# caphumidsens_rev4.net
KiCad netlist of a schematic drawn in EAGLE
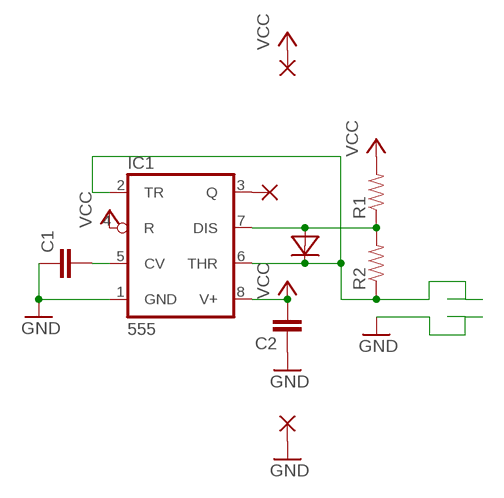
[diagram p0: schematic, sheet 1]

(export (version "E")
  (design (tool "Eeschema 10.0.6"))
  (components
    (comp (ref "C1")
      (value "CAP0805")
      (footprint "eagle-import:0805")
      (libsource (lib "eagle-import") (part "CAP0805"))
    )
    (comp (ref "C2")
      (value "CAP0805")
      (footprint "eagle-import:0805")
      (libsource (lib "eagle-import") (part "CAP0805"))
    )
    (comp (ref "D1")
      (value "DIODE_0805")
      (footprint "eagle-import:DIODE_0805")
      (libsource (lib "eagle-import") (part "DIODE_0805"))
    )
    (comp (ref "GND")
      (value "WIREPADSMD2,54-5,08")
      (footprint "eagle-import:SMD1,27-2,54")
      (libsource (lib "eagle-import") (part "SMD2"))
    )
    (comp (ref "IC1")
      (value "555")
      (footprint "eagle-import:SO08")
      (libsource (lib "eagle-import") (part "555DNE"))
    )
    (comp (ref "OUT")
      (value "WIREPADSMD2,54-5,08")
      (footprint "eagle-import:SMD1,27-2,54")
      (libsource (lib "eagle-import") (part "SMD2"))
    )
    (comp (ref "R1")
      (value "RESISTOR0805-RES")
      (footprint "eagle-import:0805")
      (libsource (lib "eagle-import") (part "RESISTOR0805-RES"))
    )
    (comp (ref "R2")
      (value "RESISTOR0805-RES")
      (footprint "eagle-import:0805")
      (libsource (lib "eagle-import") (part "RESISTOR0805-RES"))
    )
    (comp (ref "VCC")
      (value "WIREPADSMD2,54-5,08")
      (footprint "eagle-import:SMD1,27-2,54")
      (libsource (lib "eagle-import") (part "SMD2"))
    )
  )
  (nets
    (net (code "1") (name "GND") (class "Default")
      (node (ref "C1") (pin "1") (pinfunction "1_1") (pintype "passive"))
      (node (ref "C2") (pin "1") (pinfunction "1_1") (pintype "passive"))
      (node (ref "GND") (pin "1") (pinfunction "P_1") (pintype "passive"))
      (node (ref "IC1") (pin "1") (pinfunction "GND_1") (pintype "power_in"))
    )
    (net (code "2") (name "Net-(D1-A)") (class "Default")
      (node (ref "D1") (pin "2") (pinfunction "A_2") (pintype "passive"))
      (node (ref "IC1") (pin "7") (pinfunction "DIS_7") (pintype "input"))
      (node (ref "R1") (pin "1") (pinfunction "1_1") (pintype "passive"))
      (node (ref "R2") (pin "2") (pinfunction "2_2") (pintype "passive"))
    )
    (net (code "3") (name "Net-(D1-C)") (class "Default")
      (node (ref "D1") (pin "1") (pinfunction "C_1") (pintype "passive"))
      (node (ref "IC1") (pin "2") (pinfunction "TR_2") (pintype "input"))
      (node (ref "IC1") (pin "6") (pinfunction "THR_6") (pintype "input"))
      (node (ref "R2") (pin "1") (pinfunction "1_1") (pintype "passive"))
    )
    (net (code "4") (name "Net-(IC1-CV)") (class "Default")
      (node (ref "C1") (pin "2") (pinfunction "2_2") (pintype "passive"))
      (node (ref "IC1") (pin "5") (pinfunction "CV_5") (pintype "input"))
    )
    (net (code "5") (name "Net-(IC1-Q)") (class "Default")
      (node (ref "IC1") (pin "3") (pinfunction "Q_3") (pintype "output"))
      (node (ref "OUT") (pin "1") (pinfunction "P_1") (pintype "passive"))
    )
    (net (code "6") (name "VCC") (class "Default")
      (node (ref "C2") (pin "2") (pinfunction "2_2") (pintype "passive"))
      (node (ref "IC1") (pin "4") (pinfunction "R_4") (pintype "input"))
      (node (ref "IC1") (pin "8") (pinfunction "V+_8") (pintype "power_in"))
      (node (ref "R1") (pin "2") (pinfunction "2_2") (pintype "passive"))
      (node (ref "VCC") (pin "1") (pinfunction "P_1") (pintype "passive"))
    )
  )
)
